# board.net
KiCad netlist of a schematic drawn in EAGLE
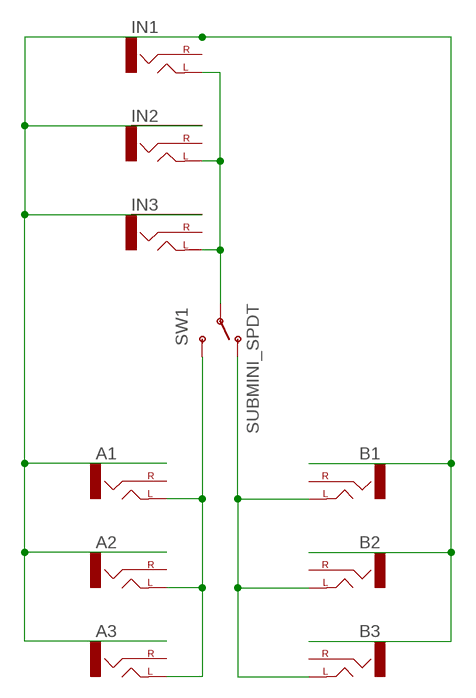
[diagram p0: schematic, sheet 1]

(export (version "E")
  (design (tool "Eeschema 10.0.6"))
  (components
    (comp (ref "A1")
      (value "THONKI-STEREO")
      (footprint "eagle-import:WQP-PJ366ST_JACK")
      (libsource (lib "eagle-import") (part "THONKI-STEREO"))
    )
    (comp (ref "A2")
      (value "THONKI-STEREO")
      (footprint "eagle-import:WQP-PJ366ST_JACK")
      (libsource (lib "eagle-import") (part "THONKI-STEREO"))
    )
    (comp (ref "A3")
      (value "THONKI-STEREO")
      (footprint "eagle-import:WQP-PJ366ST_JACK")
      (libsource (lib "eagle-import") (part "THONKI-STEREO"))
    )
    (comp (ref "B1")
      (value "THONKI-STEREO")
      (footprint "eagle-import:WQP-PJ366ST_JACK")
      (libsource (lib "eagle-import") (part "THONKI-STEREO"))
    )
    (comp (ref "B2")
      (value "THONKI-STEREO")
      (footprint "eagle-import:WQP-PJ366ST_JACK")
      (libsource (lib "eagle-import") (part "THONKI-STEREO"))
    )
    (comp (ref "B3")
      (value "THONKI-STEREO")
      (footprint "eagle-import:WQP-PJ366ST_JACK")
      (libsource (lib "eagle-import") (part "THONKI-STEREO"))
    )
    (comp (ref "IN1")
      (value "THONKI-STEREO")
      (footprint "eagle-import:WQP-PJ366ST_JACK")
      (libsource (lib "eagle-import") (part "THONKI-STEREO"))
    )
    (comp (ref "IN2")
      (value "THONKI-STEREO")
      (footprint "eagle-import:WQP-PJ366ST_JACK")
      (libsource (lib "eagle-import") (part "THONKI-STEREO"))
    )
    (comp (ref "IN3")
      (value "THONKI-STEREO")
      (footprint "eagle-import:WQP-PJ366ST_JACK")
      (libsource (lib "eagle-import") (part "THONKI-STEREO"))
    )
    (comp (ref "SW1")
      (value "SUBMINI_SPDT")
      (footprint "eagle-import:SUBMINI_TOGGLE")
      (libsource (lib "eagle-import") (part "SUBMINI_SPDT"))
    )
  )
  (nets
    (net (code "1") (name "Net-(A1-LEFT)") (class "Default")
      (node (ref "A1") (pin "P$1_TIP") (pinfunction "LEFT_P$1_TIP") (pintype "bidirectional"))
      (node (ref "A2") (pin "P$1_TIP") (pinfunction "LEFT_P$1_TIP") (pintype "bidirectional"))
      (node (ref "A3") (pin "P$1_TIP") (pinfunction "LEFT_P$1_TIP") (pintype "bidirectional"))
      (node (ref "SW1") (pin "3") (pinfunction "S_3") (pintype "passive"))
    )
    (net (code "2") (name "Net-(A1-SLEEVE)") (class "Default")
      (node (ref "A1") (pin "P$3_SLEEVE") (pinfunction "SLEEVE_P$3_SLEEVE") (pintype "bidirectional"))
      (node (ref "A2") (pin "P$3_SLEEVE") (pinfunction "SLEEVE_P$3_SLEEVE") (pintype "bidirectional"))
      (node (ref "A3") (pin "P$3_SLEEVE") (pinfunction "SLEEVE_P$3_SLEEVE") (pintype "bidirectional"))
      (node (ref "B1") (pin "P$3_SLEEVE") (pinfunction "SLEEVE_P$3_SLEEVE") (pintype "bidirectional"))
      (node (ref "B2") (pin "P$3_SLEEVE") (pinfunction "SLEEVE_P$3_SLEEVE") (pintype "bidirectional"))
      (node (ref "B3") (pin "P$3_SLEEVE") (pinfunction "SLEEVE_P$3_SLEEVE") (pintype "bidirectional"))
      (node (ref "IN1") (pin "P$3_SLEEVE") (pinfunction "SLEEVE_P$3_SLEEVE") (pintype "bidirectional"))
      (node (ref "IN2") (pin "P$3_SLEEVE") (pinfunction "SLEEVE_P$3_SLEEVE") (pintype "bidirectional"))
      (node (ref "IN3") (pin "P$3_SLEEVE") (pinfunction "SLEEVE_P$3_SLEEVE") (pintype "bidirectional"))
    )
    (net (code "3") (name "Net-(B1-LEFT)") (class "Default")
      (node (ref "B1") (pin "P$1_TIP") (pinfunction "LEFT_P$1_TIP") (pintype "bidirectional"))
      (node (ref "B2") (pin "P$1_TIP") (pinfunction "LEFT_P$1_TIP") (pintype "bidirectional"))
      (node (ref "B3") (pin "P$1_TIP") (pinfunction "LEFT_P$1_TIP") (pintype "bidirectional"))
      (node (ref "SW1") (pin "1") (pinfunction "O_1") (pintype "passive"))
    )
    (net (code "4") (name "Net-(IN1-LEFT)") (class "Default")
      (node (ref "IN1") (pin "P$1_TIP") (pinfunction "LEFT_P$1_TIP") (pintype "bidirectional"))
      (node (ref "IN2") (pin "P$1_TIP") (pinfunction "LEFT_P$1_TIP") (pintype "bidirectional"))
      (node (ref "IN3") (pin "P$1_TIP") (pinfunction "LEFT_P$1_TIP") (pintype "bidirectional"))
      (node (ref "SW1") (pin "COM") (pinfunction "COMMON_COM") (pintype "passive"))
    )
    (net (code "5") (name "unconnected-(A1-RIGHT-PadP$2_SWITCH)") (class "Default")
      (node (ref "A1") (pin "P$2_SWITCH") (pinfunction "RIGHT_P$2_SWITCH") (pintype "bidirectional"))
    )
    (net (code "6") (name "unconnected-(A2-RIGHT-PadP$2_SWITCH)") (class "Default")
      (node (ref "A2") (pin "P$2_SWITCH") (pinfunction "RIGHT_P$2_SWITCH") (pintype "bidirectional"))
    )
    (net (code "7") (name "unconnected-(A3-RIGHT-PadP$2_SWITCH)") (class "Default")
      (node (ref "A3") (pin "P$2_SWITCH") (pinfunction "RIGHT_P$2_SWITCH") (pintype "bidirectional"))
    )
    (net (code "8") (name "unconnected-(B1-RIGHT-PadP$2_SWITCH)") (class "Default")
      (node (ref "B1") (pin "P$2_SWITCH") (pinfunction "RIGHT_P$2_SWITCH") (pintype "bidirectional"))
    )
    (net (code "9") (name "unconnected-(B2-RIGHT-PadP$2_SWITCH)") (class "Default")
      (node (ref "B2") (pin "P$2_SWITCH") (pinfunction "RIGHT_P$2_SWITCH") (pintype "bidirectional"))
    )
    (net (code "10") (name "unconnected-(B3-RIGHT-PadP$2_SWITCH)") (class "Default")
      (node (ref "B3") (pin "P$2_SWITCH") (pinfunction "RIGHT_P$2_SWITCH") (pintype "bidirectional"))
    )
    (net (code "11") (name "unconnected-(IN1-RIGHT-PadP$2_SWITCH)") (class "Default")
      (node (ref "IN1") (pin "P$2_SWITCH") (pinfunction "RIGHT_P$2_SWITCH") (pintype "bidirectional"))
    )
    (net (code "12") (name "unconnected-(IN2-RIGHT-PadP$2_SWITCH)") (class "Default")
      (node (ref "IN2") (pin "P$2_SWITCH") (pinfunction "RIGHT_P$2_SWITCH") (pintype "bidirectional"))
    )
    (net (code "13") (name "unconnected-(IN3-RIGHT-PadP$2_SWITCH)") (class "Default")
      (node (ref "IN3") (pin "P$2_SWITCH") (pinfunction "RIGHT_P$2_SWITCH") (pintype "bidirectional"))
    )
  )
)
